# bike_sensor.net
KiCad netlist of a schematic drawn in EAGLE
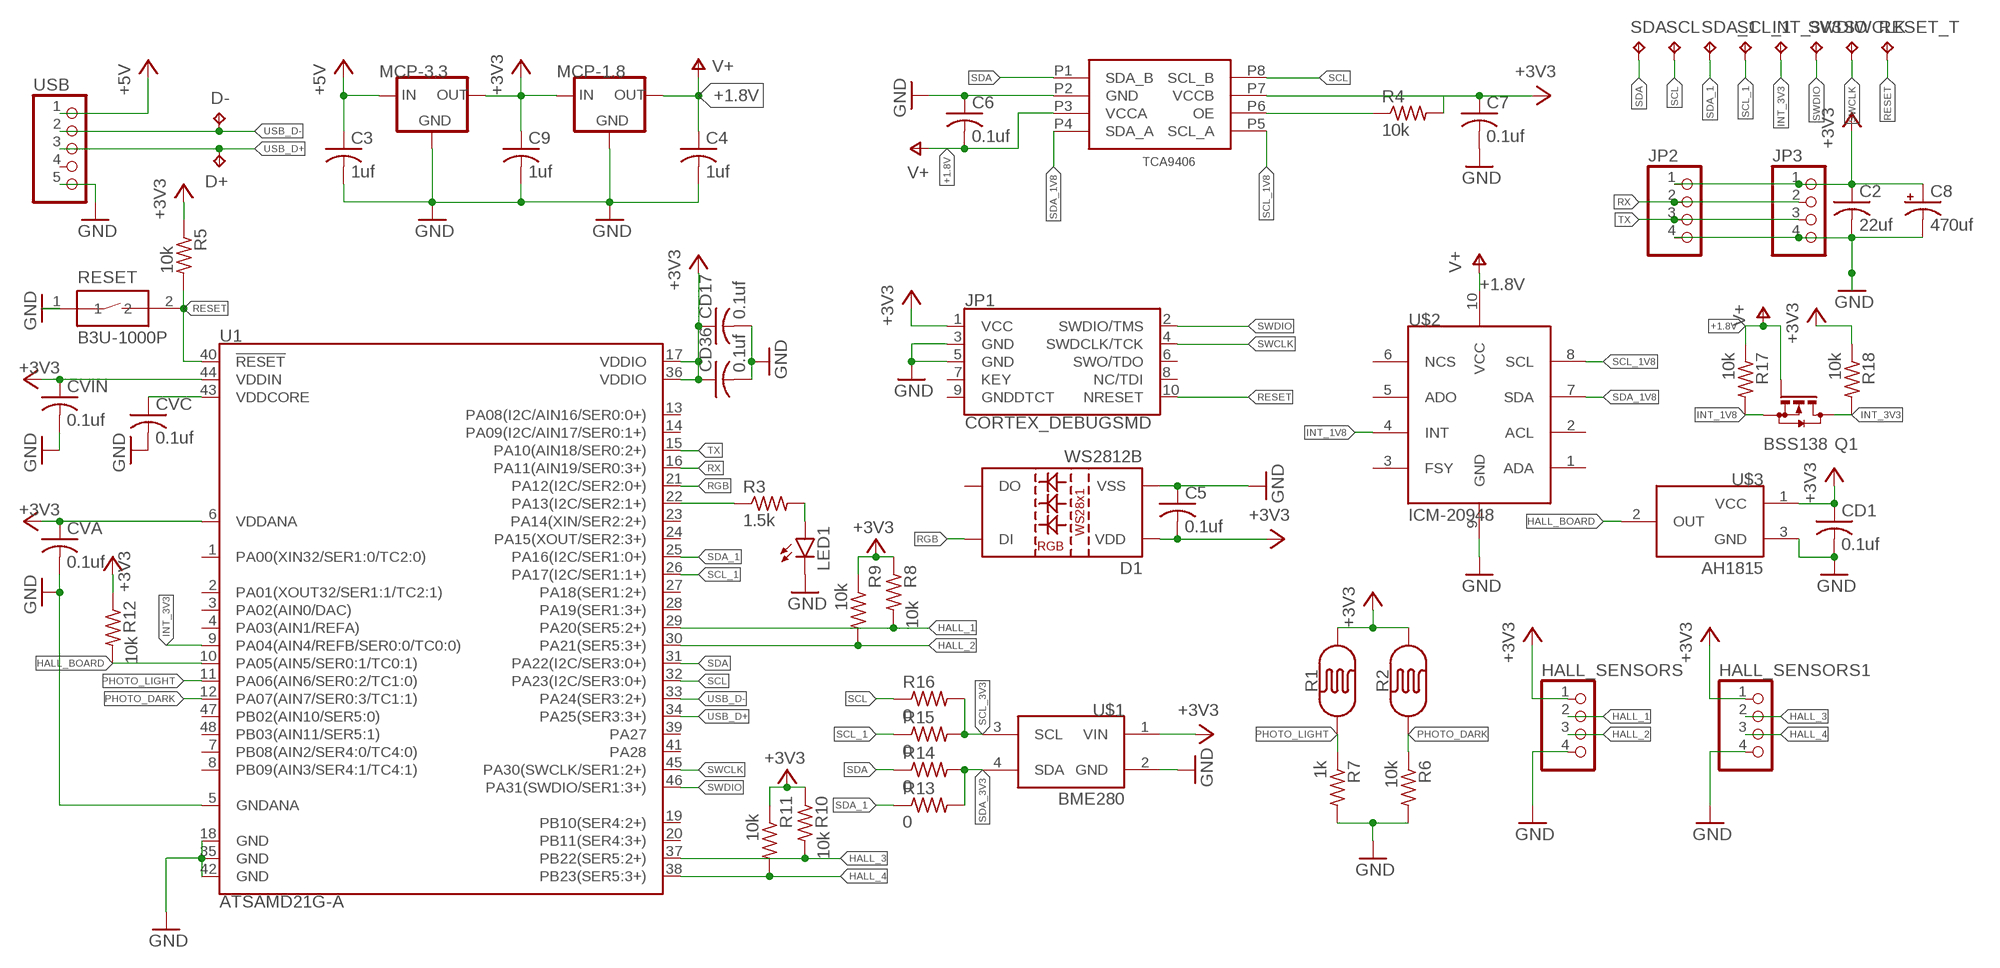
[diagram p0: schematic, sheet 1]

(export (version "E")
  (design (tool "Eeschema 10.0.6"))
  (components
    (comp (ref "C2")
      (value "22uf")
      (footprint "eagle-import:C1210")
      (libsource (lib "eagle-import") (part "C-USC1210"))
    )
    (comp (ref "C3")
      (value "1uf")
      (footprint "eagle-import:C1210")
      (libsource (lib "eagle-import") (part "C-USC1210"))
    )
    (comp (ref "C4")
      (value "1uf")
      (footprint "eagle-import:C1210")
      (libsource (lib "eagle-import") (part "C-USC1210"))
    )
    (comp (ref "C5")
      (value "0.1uf")
      (footprint "eagle-import:C0805")
      (libsource (lib "eagle-import") (part "C-USC0805"))
    )
    (comp (ref "C6")
      (value "0.1uf")
      (footprint "eagle-import:C0805")
      (libsource (lib "eagle-import") (part "C-USC0805"))
    )
    (comp (ref "C7")
      (value "0.1uf")
      (footprint "eagle-import:C0805")
      (libsource (lib "eagle-import") (part "C-USC0805"))
    )
    (comp (ref "C8")
      (value "470uf")
      (footprint "eagle-import:UD-8X10_NICHICON")
      (libsource (lib "eagle-import") (part "CPOL-USUD-8X10"))
    )
    (comp (ref "C9")
      (value "1uf")
      (footprint "eagle-import:C1210")
      (libsource (lib "eagle-import") (part "C-USC1210"))
    )
    (comp (ref "CD1")
      (value "0.1uf")
      (footprint "eagle-import:C0805")
      (libsource (lib "eagle-import") (part "C-USC0805"))
    )
    (comp (ref "CD17")
      (value "0.1uf")
      (footprint "eagle-import:C0805")
      (libsource (lib "eagle-import") (part "C-USC0805"))
    )
    (comp (ref "CD36")
      (value "0.1uf")
      (footprint "eagle-import:C0805")
      (libsource (lib "eagle-import") (part "C-USC0805"))
    )
    (comp (ref "CVA")
      (value "0.1uf")
      (footprint "eagle-import:C0805")
      (libsource (lib "eagle-import") (part "C-USC0805"))
    )
    (comp (ref "CVC")
      (value "0.1uf")
      (footprint "eagle-import:C0805")
      (libsource (lib "eagle-import") (part "C-USC0805"))
    )
    (comp (ref "CVIN")
      (value "0.1uf")
      (footprint "eagle-import:C0805")
      (libsource (lib "eagle-import") (part "C-USC0805"))
    )
    (comp (ref "D+")
      (value "TPB1,27")
      (footprint "eagle-import:B1,27")
      (libsource (lib "eagle-import") (part "TPB1,27"))
    )
    (comp (ref "D-")
      (value "TPB1,27")
      (footprint "eagle-import:B1,27")
      (libsource (lib "eagle-import") (part "TPB1,27"))
    )
    (comp (ref "D1")
      (value "WS2812B")
      (footprint "eagle-import:WS2812B")
      (libsource (lib "eagle-import") (part "WS2812B"))
    )
    (comp (ref "HALL_SENSORS")
      (value "PINHD-1X4")
      (footprint "eagle-import:1X04")
      (libsource (lib "eagle-import") (part "PINHD-1X4"))
    )
    (comp (ref "HALL_SENSORS1")
      (value "PINHD-1X4")
      (footprint "eagle-import:1X04")
      (libsource (lib "eagle-import") (part "PINHD-1X4"))
    )
    (comp (ref "INT_3V3")
      (value "TPB1,27")
      (footprint "eagle-import:B1,27")
      (libsource (lib "eagle-import") (part "TPB1,27"))
    )
    (comp (ref "JP1")
      (value "CORTEX_DEBUGSMD")
      (footprint "eagle-import:SAMTECH_FTSH-105-01")
      (libsource (lib "eagle-import") (part "CORTEX_DEBUGSMD"))
    )
    (comp (ref "JP2")
      (value "PINHD-1X4")
      (footprint "eagle-import:1X04")
      (libsource (lib "eagle-import") (part "PINHD-1X4"))
    )
    (comp (ref "JP3")
      (value "PINHD-1X4")
      (footprint "eagle-import:1X04")
      (libsource (lib "eagle-import") (part "PINHD-1X4"))
    )
    (comp (ref "LED1")
      (value "LEDCHIPLED_0805")
      (footprint "eagle-import:CHIPLED_0805")
      (libsource (lib "eagle-import") (part "LEDCHIPLED_0805"))
    )
    (comp (ref "MCP-1.8")
      (value "XC63FPM")
      (footprint "eagle-import:SOT23")
      (libsource (lib "eagle-import") (part "XC63FPM"))
    )
    (comp (ref "MCP-3.3")
      (value "XC63FPM")
      (footprint "eagle-import:SOT23")
      (libsource (lib "eagle-import") (part "XC63FPM"))
    )
    (comp (ref "Q1")
      (value "BSS138")
      (footprint "eagle-import:SOT23")
      (libsource (lib "eagle-import") (part "BSS123"))
    )
    (comp (ref "R1")
      (value "PHOTOCELLPTH")
      (footprint "eagle-import:PHOTOCELL")
      (libsource (lib "eagle-import") (part "PHOTOCELLPTH"))
    )
    (comp (ref "R2")
      (value "PHOTOCELLPTH")
      (footprint "eagle-import:PHOTOCELL")
      (libsource (lib "eagle-import") (part "PHOTOCELLPTH"))
    )
    (comp (ref "R3")
      (value "1.5k")
      (footprint "eagle-import:R0805")
      (libsource (lib "eagle-import") (part "R-US_R0805"))
    )
    (comp (ref "R4")
      (value "10k")
      (footprint "eagle-import:R0805")
      (libsource (lib "eagle-import") (part "R-US_R0805"))
    )
    (comp (ref "R5")
      (value "10k")
      (footprint "eagle-import:R0805")
      (libsource (lib "eagle-import") (part "R-US_R0805"))
    )
    (comp (ref "R6")
      (value "10k")
      (footprint "eagle-import:R0805")
      (libsource (lib "eagle-import") (part "R-US_R0805"))
    )
    (comp (ref "R7")
      (value "1k")
      (footprint "eagle-import:R0805")
      (libsource (lib "eagle-import") (part "R-US_R0805"))
    )
    (comp (ref "R8")
      (value "10k")
      (footprint "eagle-import:R0805")
      (libsource (lib "eagle-import") (part "R-US_R0805"))
    )
    (comp (ref "R9")
      (value "10k")
      (footprint "eagle-import:R0805")
      (libsource (lib "eagle-import") (part "R-US_R0805"))
    )
    (comp (ref "R10")
      (value "10k")
      (footprint "eagle-import:R0805")
      (libsource (lib "eagle-import") (part "R-US_R0805"))
    )
    (comp (ref "R11")
      (value "10k")
      (footprint "eagle-import:R0805")
      (libsource (lib "eagle-import") (part "R-US_R0805"))
    )
    (comp (ref "R12")
      (value "10k")
      (footprint "eagle-import:R0805")
      (libsource (lib "eagle-import") (part "R-US_R0805"))
    )
    (comp (ref "R13")
      (value "0")
      (footprint "eagle-import:R0603")
      (libsource (lib "eagle-import") (part "R-US_R0603"))
    )
    (comp (ref "R14")
      (value "0")
      (footprint "eagle-import:R0603")
      (libsource (lib "eagle-import") (part "R-US_R0603"))
    )
    (comp (ref "R15")
      (value "0")
      (footprint "eagle-import:R0603")
      (libsource (lib "eagle-import") (part "R-US_R0603"))
    )
    (comp (ref "R16")
      (value "0")
      (footprint "eagle-import:R0603")
      (libsource (lib "eagle-import") (part "R-US_R0603"))
    )
    (comp (ref "R17")
      (value "10k")
      (footprint "eagle-import:R0805")
      (libsource (lib "eagle-import") (part "R-US_R0805"))
    )
    (comp (ref "R18")
      (value "10k")
      (footprint "eagle-import:R0805")
      (libsource (lib "eagle-import") (part "R-US_R0805"))
    )
    (comp (ref "RESET")
      (value "B3U-1000P")
      (footprint "eagle-import:B3U-1000P")
      (fields
        (field (name "DIGI_KEY_PART_NUMBER") "SW1020CT-ND")
        (field (name "MANUFACTURER") "Omron Electronics Inc-EMC Div")
        (field (name "CREATED_BY") "PCBLayout.com")
      )
      (libsource (lib "eagle-import") (part "B3U-1000P"))
    )
    (comp (ref "RESET_T")
      (value "TPB1,27")
      (footprint "eagle-import:B1,27")
      (libsource (lib "eagle-import") (part "TPB1,27"))
    )
    (comp (ref "SCL")
      (value "TPB1,27")
      (footprint "eagle-import:B1,27")
      (libsource (lib "eagle-import") (part "TPB1,27"))
    )
    (comp (ref "SCL_1")
      (value "TPB1,27")
      (footprint "eagle-import:B1,27")
      (libsource (lib "eagle-import") (part "TPB1,27"))
    )
    (comp (ref "SDA")
      (value "TPB1,27")
      (footprint "eagle-import:B1,27")
      (libsource (lib "eagle-import") (part "TPB1,27"))
    )
    (comp (ref "SDA_1")
      (value "TPB1,27")
      (footprint "eagle-import:B1,27")
      (libsource (lib "eagle-import") (part "TPB1,27"))
    )
    (comp (ref "SWCLK")
      (value "TPB1,27")
      (footprint "eagle-import:B1,27")
      (libsource (lib "eagle-import") (part "TPB1,27"))
    )
    (comp (ref "SWDIO")
      (value "TPB1,27")
      (footprint "eagle-import:B1,27")
      (libsource (lib "eagle-import") (part "TPB1,27"))
    )
    (comp (ref "U$1")
      (value "BMP280")
      (footprint "eagle-import:BME280-BOARD")
      (libsource (lib "eagle-import") (part "BMP280"))
    )
    (comp (ref "U$2")
      (value "ICM-20948")
      (footprint "eagle-import:ICM-20948-BOARD")
      (libsource (lib "eagle-import") (part "ICM-20948"))
    )
    (comp (ref "U$3")
      (value "AH1815")
      (footprint "eagle-import:SOT23")
      (libsource (lib "eagle-import") (part "AH1815"))
    )
    (comp (ref "U$5")
      (value "TCA9406")
      (footprint "eagle-import:DCU")
      (libsource (lib "eagle-import") (part "TCA9406"))
    )
    (comp (ref "U1")
      (value "ATSAMD21G-A")
      (footprint "eagle-import:TQFP-48")
      (libsource (lib "eagle-import") (part "ATSAMD21G-A"))
    )
    (comp (ref "USB")
      (value "PINHD-1X5")
      (footprint "eagle-import:1X05")
      (libsource (lib "eagle-import") (part "PINHD-1X5"))
    )
  )
  (nets
    (net (code "1") (name "+1.8V") (class "Default")
      (node (ref "C4") (pin "1") (pinfunction "1_1") (pintype "passive"))
      (node (ref "C6") (pin "2") (pinfunction "2_2") (pintype "passive"))
      (node (ref "MCP-1.8") (pin "2") (pinfunction "OUT_2") (pintype "passive"))
      (node (ref "Q1") (pin "1") (pinfunction "G_1") (pintype "passive"))
      (node (ref "R17") (pin "1") (pinfunction "1_1") (pintype "passive"))
      (node (ref "U$2") (pin "10") (pinfunction "VCC_10") (pintype "power_in"))
      (node (ref "U$5") (pin "P3") (pinfunction "VCCA_P3") (pintype "bidirectional"))
    )
    (net (code "2") (name "+3V3") (class "Default")
      (node (ref "C2") (pin "1") (pinfunction "1_1") (pintype "passive"))
      (node (ref "C5") (pin "2") (pinfunction "2_2") (pintype "passive"))
      (node (ref "C7") (pin "1") (pinfunction "1_1") (pintype "passive"))
      (node (ref "C8") (pin "+") (pinfunction "+_+") (pintype "passive"))
      (node (ref "C9") (pin "1") (pinfunction "1_1") (pintype "passive"))
      (node (ref "CD1") (pin "1") (pinfunction "1_1") (pintype "passive"))
      (node (ref "CD17") (pin "1") (pinfunction "1_1") (pintype "passive"))
      (node (ref "CD36") (pin "1") (pinfunction "1_1") (pintype "passive"))
      (node (ref "CVA") (pin "1") (pinfunction "1_1") (pintype "passive"))
      (node (ref "CVIN") (pin "1") (pinfunction "1_1") (pintype "passive"))
      (node (ref "D1") (pin "1") (pinfunction "VDD_1") (pintype "bidirectional"))
      (node (ref "HALL_SENSORS") (pin "1") (pinfunction "1_1") (pintype "passive"))
      (node (ref "HALL_SENSORS1") (pin "1") (pinfunction "1_1") (pintype "passive"))
      (node (ref "JP1") (pin "1") (pinfunction "VCC_1") (pintype "bidirectional"))
      (node (ref "JP2") (pin "1") (pinfunction "1_1") (pintype "passive"))
      (node (ref "JP3") (pin "1") (pinfunction "1_1") (pintype "passive"))
      (node (ref "MCP-1.8") (pin "3") (pinfunction "IN_3") (pintype "input"))
      (node (ref "MCP-3.3") (pin "2") (pinfunction "OUT_2") (pintype "passive"))
      (node (ref "R1") (pin "2") (pinfunction "P$2_2") (pintype "bidirectional"))
      (node (ref "R10") (pin "1") (pinfunction "1_1") (pintype "passive"))
      (node (ref "R11") (pin "1") (pinfunction "1_1") (pintype "passive"))
      (node (ref "R12") (pin "1") (pinfunction "1_1") (pintype "passive"))
      (node (ref "R18") (pin "1") (pinfunction "1_1") (pintype "passive"))
      (node (ref "R2") (pin "2") (pinfunction "P$2_2") (pintype "bidirectional"))
      (node (ref "R4") (pin "2") (pinfunction "2_2") (pintype "passive"))
      (node (ref "R5") (pin "1") (pinfunction "1_1") (pintype "passive"))
      (node (ref "R8") (pin "1") (pinfunction "1_1") (pintype "passive"))
      (node (ref "R9") (pin "1") (pinfunction "1_1") (pintype "passive"))
      (node (ref "U$1") (pin "1") (pinfunction "VIN_1") (pintype "bidirectional"))
      (node (ref "U$3") (pin "1") (pinfunction "VCC_1") (pintype "power_in"))
      (node (ref "U$5") (pin "P7") (pinfunction "VCCB_P7") (pintype "bidirectional"))
      (node (ref "U1") (pin "17") (pinfunction "VDDIO_17") (pintype "bidirectional"))
      (node (ref "U1") (pin "36") (pinfunction "VDDIO_36") (pintype "bidirectional"))
      (node (ref "U1") (pin "44") (pinfunction "VDDIN_44") (pintype "bidirectional"))
      (node (ref "U1") (pin "6") (pinfunction "VDDANA_6") (pintype "bidirectional"))
    )
    (net (code "3") (name "+5V") (class "Default")
      (node (ref "C3") (pin "1") (pinfunction "1_1") (pintype "passive"))
      (node (ref "MCP-3.3") (pin "3") (pinfunction "IN_3") (pintype "input"))
      (node (ref "USB") (pin "1") (pinfunction "1_1") (pintype "passive"))
    )
    (net (code "4") (name "GND") (class "Default")
      (node (ref "C2") (pin "2") (pinfunction "2_2") (pintype "passive"))
      (node (ref "C3") (pin "2") (pinfunction "2_2") (pintype "passive"))
      (node (ref "C4") (pin "2") (pinfunction "2_2") (pintype "passive"))
      (node (ref "C5") (pin "1") (pinfunction "1_1") (pintype "passive"))
      (node (ref "C6") (pin "1") (pinfunction "1_1") (pintype "passive"))
      (node (ref "C7") (pin "2") (pinfunction "2_2") (pintype "passive"))
      (node (ref "C8") (pin "-") (pinfunction "-_-") (pintype "passive"))
      (node (ref "C9") (pin "2") (pinfunction "2_2") (pintype "passive"))
      (node (ref "CD1") (pin "2") (pinfunction "2_2") (pintype "passive"))
      (node (ref "CD17") (pin "2") (pinfunction "2_2") (pintype "passive"))
      (node (ref "CD36") (pin "2") (pinfunction "2_2") (pintype "passive"))
      (node (ref "CVA") (pin "2") (pinfunction "2_2") (pintype "passive"))
      (node (ref "CVC") (pin "2") (pinfunction "2_2") (pintype "passive"))
      (node (ref "CVIN") (pin "2") (pinfunction "2_2") (pintype "passive"))
      (node (ref "D1") (pin "3") (pinfunction "VSS_3") (pintype "bidirectional"))
      (node (ref "HALL_SENSORS") (pin "4") (pinfunction "4_4") (pintype "passive"))
      (node (ref "HALL_SENSORS1") (pin "4") (pinfunction "4_4") (pintype "passive"))
      (node (ref "JP1") (pin "3") (pinfunction "GND_3") (pintype "bidirectional"))
      (node (ref "JP1") (pin "5") (pinfunction "GND_5") (pintype "bidirectional"))
      (node (ref "JP2") (pin "4") (pinfunction "4_4") (pintype "passive"))
      (node (ref "JP3") (pin "4") (pinfunction "4_4") (pintype "passive"))
      (node (ref "LED1") (pin "C") (pinfunction "C_C") (pintype "passive"))
      (node (ref "MCP-1.8") (pin "1") (pinfunction "GND_1") (pintype "input"))
      (node (ref "MCP-3.3") (pin "1") (pinfunction "GND_1") (pintype "input"))
      (node (ref "R6") (pin "2") (pinfunction "2_2") (pintype "passive"))
      (node (ref "R7") (pin "2") (pinfunction "2_2") (pintype "passive"))
      (node (ref "RESET") (pin "1") (pinfunction "1_1") (pintype "passive"))
      (node (ref "U$1") (pin "2") (pinfunction "GND_2") (pintype "bidirectional"))
      (node (ref "U$2") (pin "9") (pinfunction "GND_9") (pintype "bidirectional"))
      (node (ref "U$3") (pin "3") (pinfunction "GND_3") (pintype "power_in"))
      (node (ref "U$5") (pin "P2") (pinfunction "GND_P2") (pintype "bidirectional"))
      (node (ref "U1") (pin "18") (pinfunction "GND_18") (pintype "bidirectional"))
      (node (ref "U1") (pin "35") (pinfunction "GND_35") (pintype "bidirectional"))
      (node (ref "U1") (pin "42") (pinfunction "GND_42") (pintype "bidirectional"))
      (node (ref "U1") (pin "5") (pinfunction "GNDANA_5") (pintype "bidirectional"))
      (node (ref "USB") (pin "5") (pinfunction "5_5") (pintype "passive"))
    )
    (net (code "5") (name "HALL_1") (class "Default")
      (node (ref "HALL_SENSORS") (pin "2") (pinfunction "2_2") (pintype "passive"))
      (node (ref "R8") (pin "2") (pinfunction "2_2") (pintype "passive"))
      (node (ref "U1") (pin "29") (pinfunction "PA20(SER5:2+)_29") (pintype "bidirectional"))
    )
    (net (code "6") (name "HALL_2") (class "Default")
      (node (ref "HALL_SENSORS") (pin "3") (pinfunction "3_3") (pintype "passive"))
      (node (ref "R9") (pin "2") (pinfunction "2_2") (pintype "passive"))
      (node (ref "U1") (pin "30") (pinfunction "PA21(SER5:3+)_30") (pintype "bidirectional"))
    )
    (net (code "7") (name "HALL_3") (class "Default")
      (node (ref "HALL_SENSORS1") (pin "2") (pinfunction "2_2") (pintype "passive"))
      (node (ref "R10") (pin "2") (pinfunction "2_2") (pintype "passive"))
      (node (ref "U1") (pin "37") (pinfunction "PB22(SER5:2+)_37") (pintype "bidirectional"))
    )
    (net (code "8") (name "HALL_4") (class "Default")
      (node (ref "HALL_SENSORS1") (pin "3") (pinfunction "3_3") (pintype "passive"))
      (node (ref "R11") (pin "2") (pinfunction "2_2") (pintype "passive"))
      (node (ref "U1") (pin "38") (pinfunction "PB23(SER5:3+)_38") (pintype "bidirectional"))
    )
    (net (code "9") (name "HALL_BOARD") (class "Default")
      (node (ref "R12") (pin "2") (pinfunction "2_2") (pintype "passive"))
      (node (ref "U$3") (pin "2") (pinfunction "OUT_2") (pintype "output"))
      (node (ref "U1") (pin "10") (pinfunction "PA05(AIN5/SER0:1/TC0:1)_10") (pintype "bidirectional"))
    )
    (net (code "10") (name "INT_1V8") (class "Default")
      (node (ref "Q1") (pin "2") (pinfunction "S_2") (pintype "passive"))
      (node (ref "R17") (pin "2") (pinfunction "2_2") (pintype "passive"))
      (node (ref "U$2") (pin "4") (pinfunction "INT_4") (pintype "bidirectional"))
    )
    (net (code "11") (name "INT_3V3") (class "Default")
      (node (ref "INT_3V3") (pin "TP") (pinfunction "TP_TP") (pintype "input"))
      (node (ref "Q1") (pin "3") (pinfunction "D_3") (pintype "passive"))
      (node (ref "R18") (pin "2") (pinfunction "2_2") (pintype "passive"))
      (node (ref "U1") (pin "9") (pinfunction "PA04(AIN4/REFB/SER0:0/TC0:0)_9") (pintype "bidirectional"))
    )
    (net (code "12") (name "Net-(LED1-PadA)") (class "Default")
      (node (ref "LED1") (pin "A") (pinfunction "A_A") (pintype "passive"))
      (node (ref "R3") (pin "2") (pinfunction "2_2") (pintype "passive"))
    )
    (net (code "13") (name "Net-(U$5-OE)") (class "Default")
      (node (ref "R4") (pin "1") (pinfunction "1_1") (pintype "passive"))
      (node (ref "U$5") (pin "P6") (pinfunction "OE_P6") (pintype "bidirectional"))
    )
    (net (code "14") (name "Net-(U1-PA13(I2C{slash}SER2:1+))") (class "Default")
      (node (ref "R3") (pin "1") (pinfunction "1_1") (pintype "passive"))
      (node (ref "U1") (pin "22") (pinfunction "PA13(I2C/SER2:1+)_22") (pintype "bidirectional"))
    )
    (net (code "15") (name "Net-(U1-VDDCORE)") (class "Default")
      (node (ref "CVC") (pin "1") (pinfunction "1_1") (pintype "passive"))
      (node (ref "U1") (pin "43") (pinfunction "VDDCORE_43") (pintype "bidirectional"))
    )
    (net (code "16") (name "PHOTO_DARK") (class "Default")
      (node (ref "R2") (pin "1") (pinfunction "P$1_1") (pintype "bidirectional"))
      (node (ref "R6") (pin "1") (pinfunction "1_1") (pintype "passive"))
      (node (ref "U1") (pin "12") (pinfunction "PA07(AIN7/SER0:3/TC1:1)_12") (pintype "bidirectional"))
    )
    (net (code "17") (name "PHOTO_LIGHT") (class "Default")
      (node (ref "R1") (pin "1") (pinfunction "P$1_1") (pintype "bidirectional"))
      (node (ref "R7") (pin "1") (pinfunction "1_1") (pintype "passive"))
      (node (ref "U1") (pin "11") (pinfunction "PA06(AIN6/SER0:2/TC1:0)_11") (pintype "bidirectional"))
    )
    (net (code "18") (name "RESET") (class "Default")
      (node (ref "JP1") (pin "10") (pinfunction "NRESET_10") (pintype "bidirectional"))
      (node (ref "R5") (pin "2") (pinfunction "2_2") (pintype "passive"))
      (node (ref "RESET") (pin "2") (pinfunction "2_2") (pintype "passive"))
      (node (ref "RESET_T") (pin "TP") (pinfunction "TP_TP") (pintype "input"))
      (node (ref "U1") (pin "40") (pinfunction "~{RESET}_40") (pintype "bidirectional"))
    )
    (net (code "19") (name "RGB") (class "Default")
      (node (ref "D1") (pin "4") (pinfunction "DI_4") (pintype "bidirectional"))
      (node (ref "U1") (pin "21") (pinfunction "PA12(I2C/SER2:0+)_21") (pintype "bidirectional"))
    )
    (net (code "20") (name "RX") (class "Default")
      (node (ref "JP2") (pin "2") (pinfunction "2_2") (pintype "passive"))
      (node (ref "JP3") (pin "2") (pinfunction "2_2") (pintype "passive"))
      (node (ref "U1") (pin "16") (pinfunction "PA11(AIN19/SER0:3+)_16") (pintype "bidirectional"))
    )
    (net (code "21") (name "SCL") (class "Default")
      (node (ref "R16") (pin "1") (pinfunction "1_1") (pintype "passive"))
      (node (ref "SCL") (pin "TP") (pinfunction "TP_TP") (pintype "input"))
      (node (ref "U$5") (pin "P8") (pinfunction "SCL_B_P8") (pintype "bidirectional"))
      (node (ref "U1") (pin "32") (pinfunction "PA23(I2C/SER3:0+)_32") (pintype "bidirectional"))
    )
    (net (code "22") (name "SCL_1") (class "Default")
      (node (ref "R15") (pin "1") (pinfunction "1_1") (pintype "passive"))
      (node (ref "SCL_1") (pin "TP") (pinfunction "TP_TP") (pintype "input"))
      (node (ref "U1") (pin "26") (pinfunction "PA17(I2C/SER1:1+)_26") (pintype "bidirectional"))
    )
    (net (code "23") (name "SCL_1V8") (class "Default")
      (node (ref "U$2") (pin "8") (pinfunction "SCL_8") (pintype "bidirectional"))
      (node (ref "U$5") (pin "P5") (pinfunction "SCL_A_P5") (pintype "bidirectional"))
    )
    (net (code "24") (name "SCL_3V3") (class "Default")
      (node (ref "R15") (pin "2") (pinfunction "2_2") (pintype "passive"))
      (node (ref "R16") (pin "2") (pinfunction "2_2") (pintype "passive"))
      (node (ref "U$1") (pin "3") (pinfunction "SCL_3") (pintype "bidirectional"))
    )
    (net (code "25") (name "SDA") (class "Default")
      (node (ref "R14") (pin "1") (pinfunction "1_1") (pintype "passive"))
      (node (ref "SDA") (pin "TP") (pinfunction "TP_TP") (pintype "input"))
      (node (ref "U$5") (pin "P1") (pinfunction "SDA_B_P1") (pintype "bidirectional"))
      (node (ref "U1") (pin "31") (pinfunction "PA22(I2C/SER3:0+)_31") (pintype "bidirectional"))
    )
    (net (code "26") (name "SDA_1") (class "Default")
      (node (ref "R13") (pin "1") (pinfunction "1_1") (pintype "passive"))
      (node (ref "SDA_1") (pin "TP") (pinfunction "TP_TP") (pintype "input"))
      (node (ref "U1") (pin "25") (pinfunction "PA16(I2C/SER1:0+)_25") (pintype "bidirectional"))
    )
    (net (code "27") (name "SDA_1V8") (class "Default")
      (node (ref "U$2") (pin "7") (pinfunction "SDA_7") (pintype "bidirectional"))
      (node (ref "U$5") (pin "P4") (pinfunction "SDA_A_P4") (pintype "bidirectional"))
    )
    (net (code "28") (name "SDA_3V3") (class "Default")
      (node (ref "R13") (pin "2") (pinfunction "2_2") (pintype "passive"))
      (node (ref "R14") (pin "2") (pinfunction "2_2") (pintype "passive"))
      (node (ref "U$1") (pin "4") (pinfunction "SDA_4") (pintype "bidirectional"))
    )
    (net (code "29") (name "SWCLK") (class "Default")
      (node (ref "JP1") (pin "4") (pinfunction "SWDCLK/TCK_4") (pintype "bidirectional"))
      (node (ref "SWCLK") (pin "TP") (pinfunction "TP_TP") (pintype "input"))
      (node (ref "U1") (pin "45") (pinfunction "PA30(SWCLK/SER1:2+)_45") (pintype "bidirectional"))
    )
    (net (code "30") (name "SWDIO") (class "Default")
      (node (ref "JP1") (pin "2") (pinfunction "SWDIO/TMS_2") (pintype "bidirectional"))
      (node (ref "SWDIO") (pin "TP") (pinfunction "TP_TP") (pintype "input"))
      (node (ref "U1") (pin "46") (pinfunction "PA31(SWDIO/SER1:3+)_46") (pintype "bidirectional"))
    )
    (net (code "31") (name "TX") (class "Default")
      (node (ref "JP2") (pin "3") (pinfunction "3_3") (pintype "passive"))
      (node (ref "JP3") (pin "3") (pinfunction "3_3") (pintype "passive"))
      (node (ref "U1") (pin "15") (pinfunction "PA10(AIN18/SER0:2+)_15") (pintype "bidirectional"))
    )
    (net (code "32") (name "USB_D+") (class "Default")
      (node (ref "D+") (pin "TP") (pinfunction "TP_TP") (pintype "input"))
      (node (ref "U1") (pin "34") (pinfunction "PA25(SER3:3+)_34") (pintype "bidirectional"))
      (node (ref "USB") (pin "3") (pinfunction "3_3") (pintype "passive"))
    )
    (net (code "33") (name "USB_D-") (class "Default")
      (node (ref "D-") (pin "TP") (pinfunction "TP_TP") (pintype "input"))
      (node (ref "U1") (pin "33") (pinfunction "PA24(SER3:2+)_33") (pintype "bidirectional"))
      (node (ref "USB") (pin "2") (pinfunction "2_2") (pintype "passive"))
    )
    (net (code "34") (name "unconnected-(D1-DO-Pad2)") (class "Default")
      (node (ref "D1") (pin "2") (pinfunction "DO_2") (pintype "bidirectional"))
    )
    (net (code "35") (name "unconnected-(JP1-GNDDTCT-Pad9)") (class "Default")
      (node (ref "JP1") (pin "9") (pinfunction "GNDDTCT_9") (pintype "bidirectional"))
    )
    (net (code "36") (name "unconnected-(JP1-KEY-Pad7)") (class "Default")
      (node (ref "JP1") (pin "7") (pinfunction "KEY_7") (pintype "bidirectional"))
    )
    (net (code "37") (name "unconnected-(JP1-NC{slash}TDI-Pad8)") (class "Default")
      (node (ref "JP1") (pin "8") (pinfunction "NC/TDI_8") (pintype "bidirectional"))
    )
    (net (code "38") (name "unconnected-(JP1-SWO{slash}TDO-Pad6)") (class "Default")
      (node (ref "JP1") (pin "6") (pinfunction "SWO/TDO_6") (pintype "bidirectional"))
    )
    (net (code "39") (name "unconnected-(U$2-ACL-Pad2)") (class "Default")
      (node (ref "U$2") (pin "2") (pinfunction "ACL_2") (pintype "bidirectional"))
    )
    (net (code "40") (name "unconnected-(U$2-ADA-Pad1)") (class "Default")
      (node (ref "U$2") (pin "1") (pinfunction "ADA_1") (pintype "bidirectional"))
    )
    (net (code "41") (name "unconnected-(U$2-ADO-Pad5)") (class "Default")
      (node (ref "U$2") (pin "5") (pinfunction "ADO_5") (pintype "bidirectional"))
    )
    (net (code "42") (name "unconnected-(U$2-FSY-Pad3)") (class "Default")
      (node (ref "U$2") (pin "3") (pinfunction "FSY_3") (pintype "bidirectional"))
    )
    (net (code "43") (name "unconnected-(U$2-NCS-Pad6)") (class "Default")
      (node (ref "U$2") (pin "6") (pinfunction "NCS_6") (pintype "bidirectional"))
    )
    (net (code "44") (name "unconnected-(U1-PA00(XIN32{slash}SER1:0{slash}TC2:0)-Pad1)") (class "Default")
      (node (ref "U1") (pin "1") (pinfunction "PA00(XIN32/SER1:0/TC2:0)_1") (pintype "bidirectional"))
    )
    (net (code "45") (name "unconnected-(U1-PA01(XOUT32{slash}SER1:1{slash}TC2:1)-Pad2)") (class "Default")
      (node (ref "U1") (pin "2") (pinfunction "PA01(XOUT32/SER1:1/TC2:1)_2") (pintype "bidirectional"))
    )
    (net (code "46") (name "unconnected-(U1-PA02(AIN0{slash}DAC)-Pad3)") (class "Default")
      (node (ref "U1") (pin "3") (pinfunction "PA02(AIN0/DAC)_3") (pintype "bidirectional"))
    )
    (net (code "47") (name "unconnected-(U1-PA03(AIN1{slash}REFA)-Pad4)") (class "Default")
      (node (ref "U1") (pin "4") (pinfunction "PA03(AIN1/REFA)_4") (pintype "bidirectional"))
    )
    (net (code "48") (name "unconnected-(U1-PA08(I2C{slash}AIN16{slash}SER0:0+)-Pad13)") (class "Default")
      (node (ref "U1") (pin "13") (pinfunction "PA08(I2C/AIN16/SER0:0+)_13") (pintype "bidirectional"))
    )
    (net (code "49") (name "unconnected-(U1-PA09(I2C{slash}AIN17{slash}SER0:1+)-Pad14)") (class "Default")
      (node (ref "U1") (pin "14") (pinfunction "PA09(I2C/AIN17/SER0:1+)_14") (pintype "bidirectional"))
    )
    (net (code "50") (name "unconnected-(U1-PA14(XIN{slash}SER2:2+)-Pad23)") (class "Default")
      (node (ref "U1") (pin "23") (pinfunction "PA14(XIN/SER2:2+)_23") (pintype "bidirectional"))
    )
    (net (code "51") (name "unconnected-(U1-PA15(XOUT{slash}SER2:3+)-Pad24)") (class "Default")
      (node (ref "U1") (pin "24") (pinfunction "PA15(XOUT/SER2:3+)_24") (pintype "bidirectional"))
    )
    (net (code "52") (name "unconnected-(U1-PA18(SER1:2+)-Pad27)") (class "Default")
      (node (ref "U1") (pin "27") (pinfunction "PA18(SER1:2+)_27") (pintype "bidirectional"))
    )
    (net (code "53") (name "unconnected-(U1-PA19(SER1:3+)-Pad28)") (class "Default")
      (node (ref "U1") (pin "28") (pinfunction "PA19(SER1:3+)_28") (pintype "bidirectional"))
    )
    (net (code "54") (name "unconnected-(U1-PA27-Pad39)") (class "Default")
      (node (ref "U1") (pin "39") (pinfunction "PA27_39") (pintype "bidirectional"))
    )
    (net (code "55") (name "unconnected-(U1-PA28-Pad41)") (class "Default")
      (node (ref "U1") (pin "41") (pinfunction "PA28_41") (pintype "bidirectional"))
    )
    (net (code "56") (name "unconnected-(U1-PB02(AIN10{slash}SER5:0)-Pad47)") (class "Default")
      (node (ref "U1") (pin "47") (pinfunction "PB02(AIN10/SER5:0)_47") (pintype "bidirectional"))
    )
    (net (code "57") (name "unconnected-(U1-PB03(AIN11{slash}SER5:1)-Pad48)") (class "Default")
      (node (ref "U1") (pin "48") (pinfunction "PB03(AIN11/SER5:1)_48") (pintype "bidirectional"))
    )
    (net (code "58") (name "unconnected-(U1-PB08(AIN2{slash}SER4:0{slash}TC4:0)-Pad7)") (class "Default")
      (node (ref "U1") (pin "7") (pinfunction "PB08(AIN2/SER4:0/TC4:0)_7") (pintype "bidirectional"))
    )
    (net (code "59") (name "unconnected-(U1-PB09(AIN3{slash}SER4:1{slash}TC4:1)-Pad8)") (class "Default")
      (node (ref "U1") (pin "8") (pinfunction "PB09(AIN3/SER4:1/TC4:1)_8") (pintype "bidirectional"))
    )
    (net (code "60") (name "unconnected-(U1-PB10(SER4:2+)-Pad19)") (class "Default")
      (node (ref "U1") (pin "19") (pinfunction "PB10(SER4:2+)_19") (pintype "bidirectional"))
    )
    (net (code "61") (name "unconnected-(U1-PB11(SER4:3+)-Pad20)") (class "Default")
      (node (ref "U1") (pin "20") (pinfunction "PB11(SER4:3+)_20") (pintype "bidirectional"))
    )
    (net (code "62") (name "unconnected-(USB-Pad4)") (class "Default")
      (node (ref "USB") (pin "4") (pinfunction "4_4") (pintype "passive"))
    )
  )
)
